# flexNT2_V1_0.net
KiCad netlist of a schematic drawn in EAGLE
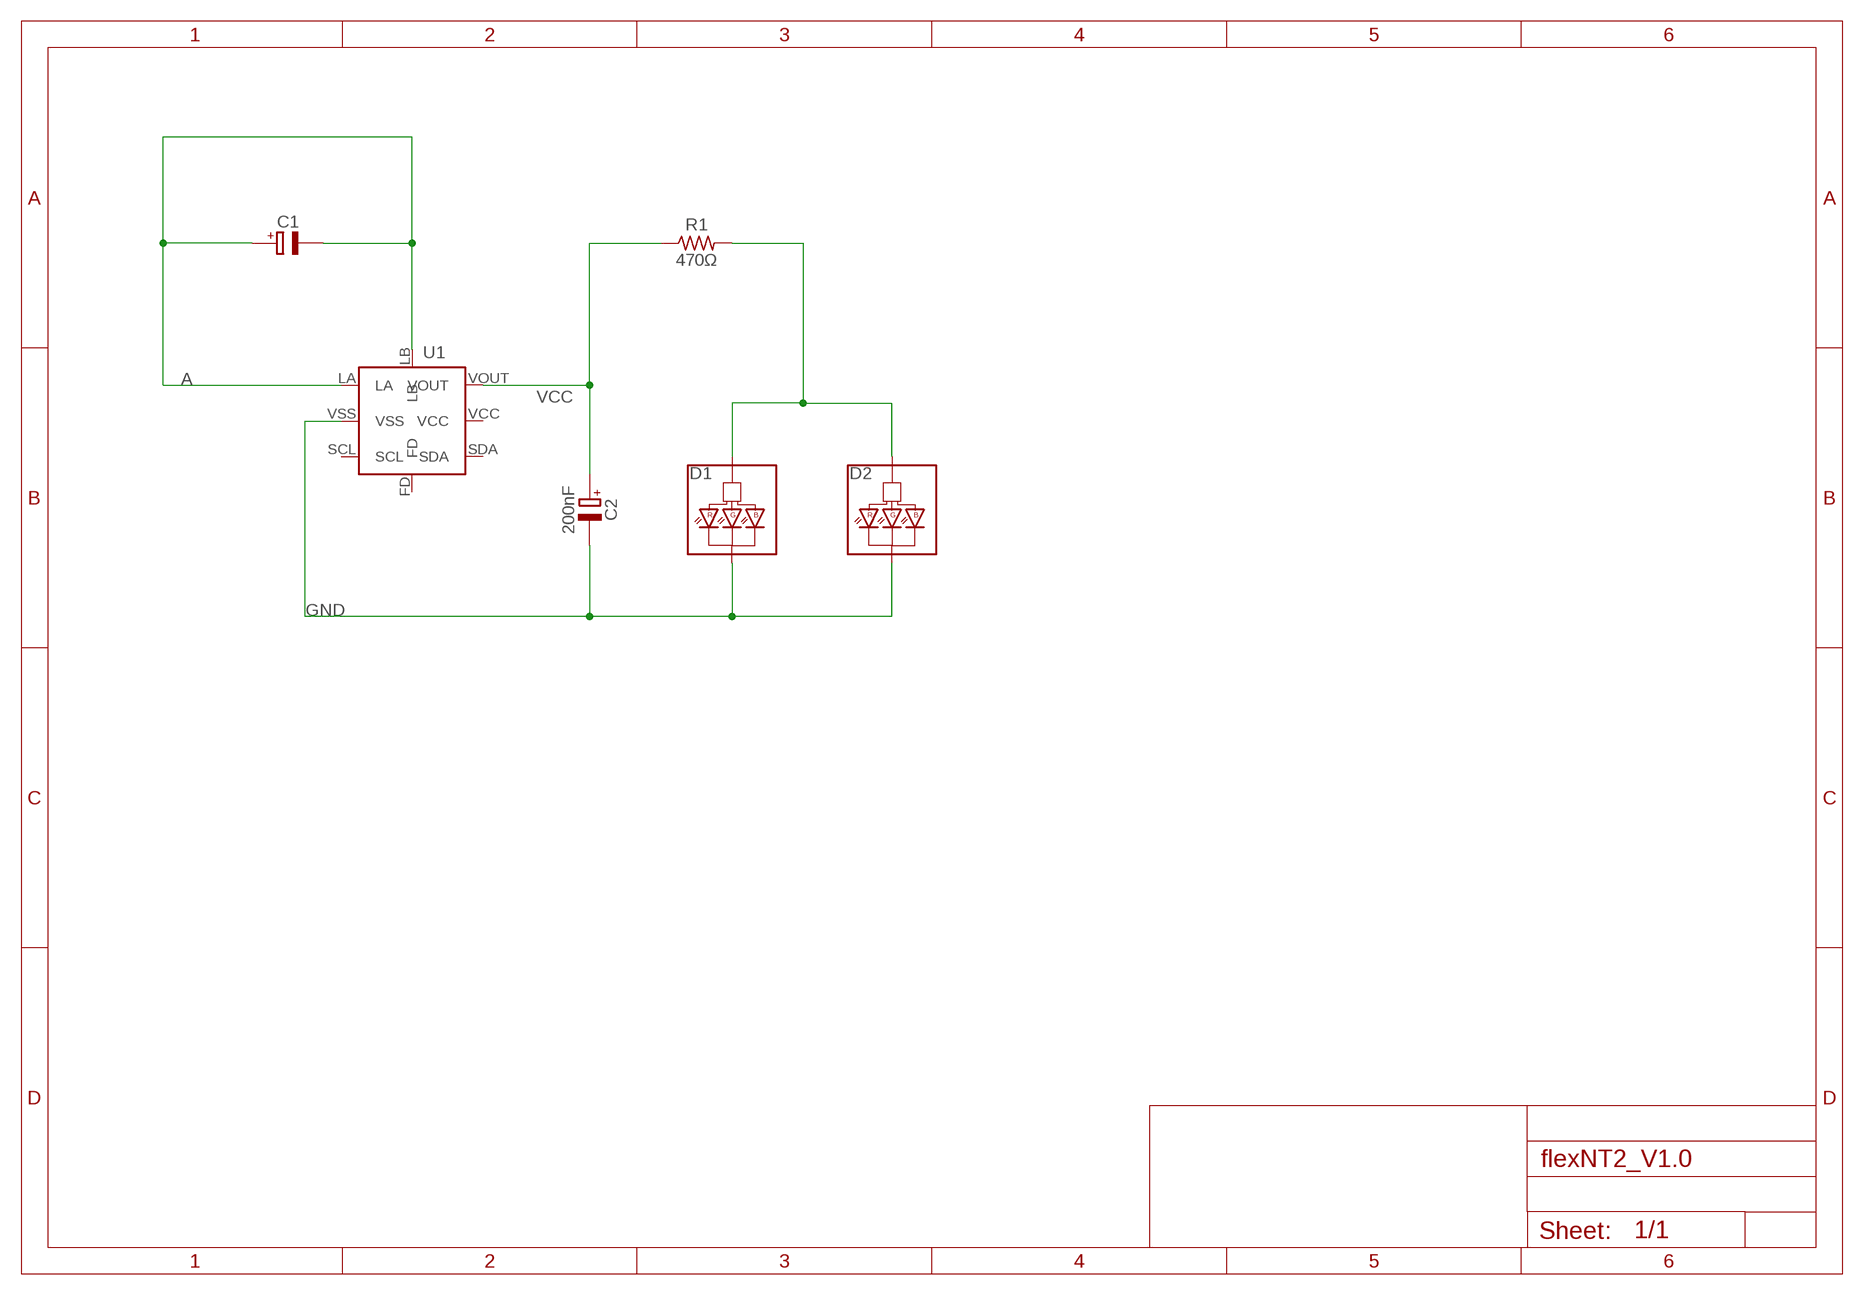
[diagram p0: schematic, sheet 1]

(export (version "E")
  (design (tool "Eeschema 10.0.6"))
  (components
    (comp (ref "C1")
      (value "C_POL_0603_FLEX")
      (footprint "eagle-import:0603_FLEX_C_POL")
      (libsource (lib "eagle-import") (part "C_POL_0603_FLEX"))
    )
    (comp (ref "C2")
      (value "200nF")
      (footprint "eagle-import:0603_FLEX_C_POL")
      (libsource (lib "eagle-import") (part "C_POL_0603_FLEX"))
    )
    (comp (ref "D1")
      (value "CZINELIGHT_0807RGBFF")
      (footprint "eagle-import:0807RGBFF_CZINELIGHT")
      (libsource (lib "eagle-import") (part "CZINELIGHT_0807RGBFF"))
    )
    (comp (ref "D2")
      (value "CZINELIGHT_0807RGBFF")
      (footprint "eagle-import:0807RGBFF_CZINELIGHT")
      (libsource (lib "eagle-import") (part "CZINELIGHT_0807RGBFF"))
    )
    (comp (ref "R1")
      (value "470Ω")
      (footprint "eagle-import:0603_FLEX")
      (libsource (lib "eagle-import") (part "R_0603_FLEX"))
    )
    (comp (ref "U1")
      (value "NTAG-I2C+")
      (footprint "eagle-import:XQFN8_NTAG-I2C+")
      (libsource (lib "eagle-import") (part "NTAG-I2C+"))
    )
  )
  (nets
    (net (code "1") (name "/A") (class "Default")
      (node (ref "C1") (pin "P$1") (pinfunction "+_P$1") (pintype "passive"))
      (node (ref "C1") (pin "P$2") (pinfunction "-_P$2") (pintype "passive"))
      (node (ref "U1") (pin "LA") (pinfunction "LA_LA") (pintype "bidirectional"))
      (node (ref "U1") (pin "LB") (pinfunction "LB_LB") (pintype "bidirectional"))
    )
    (net (code "2") (name "/GND") (class "Default")
      (node (ref "C2") (pin "P$2") (pinfunction "-_P$2") (pintype "passive"))
      (node (ref "D1") (pin "P$2") (pinfunction "C_P$2") (pintype "passive"))
      (node (ref "D2") (pin "P$2") (pinfunction "C_P$2") (pintype "passive"))
      (node (ref "U1") (pin "VSS") (pinfunction "VSS_VSS") (pintype "bidirectional"))
    )
    (net (code "3") (name "/VCC") (class "Default")
      (node (ref "C2") (pin "P$1") (pinfunction "+_P$1") (pintype "passive"))
      (node (ref "R1") (pin "P$1") (pinfunction "1_P$1") (pintype "passive"))
      (node (ref "U1") (pin "VOUT") (pinfunction "VOUT_VOUT") (pintype "bidirectional"))
    )
    (net (code "4") (name "Net-(D1-A)") (class "Default")
      (node (ref "D1") (pin "P$1") (pinfunction "A_P$1") (pintype "passive"))
      (node (ref "D2") (pin "P$1") (pinfunction "A_P$1") (pintype "passive"))
      (node (ref "R1") (pin "P$2") (pinfunction "2_P$2") (pintype "passive"))
    )
    (net (code "5") (name "unconnected-(U1-PadFD)") (class "Default")
      (node (ref "U1") (pin "FD") (pinfunction "FD_FD") (pintype "bidirectional"))
    )
    (net (code "6") (name "unconnected-(U1-PadSCL)") (class "Default")
      (node (ref "U1") (pin "SCL") (pinfunction "SCL_SCL") (pintype "bidirectional"))
    )
    (net (code "7") (name "unconnected-(U1-PadSDA)") (class "Default")
      (node (ref "U1") (pin "SDA") (pinfunction "SDA_SDA") (pintype "bidirectional"))
    )
    (net (code "8") (name "unconnected-(U1-PadVCC)") (class "Default")
      (node (ref "U1") (pin "VCC") (pinfunction "VCC_VCC") (pintype "bidirectional"))
    )
  )
)
